# 1_ATMEGA_328P_AU.net
KiCad netlist of a schematic drawn in EAGLE
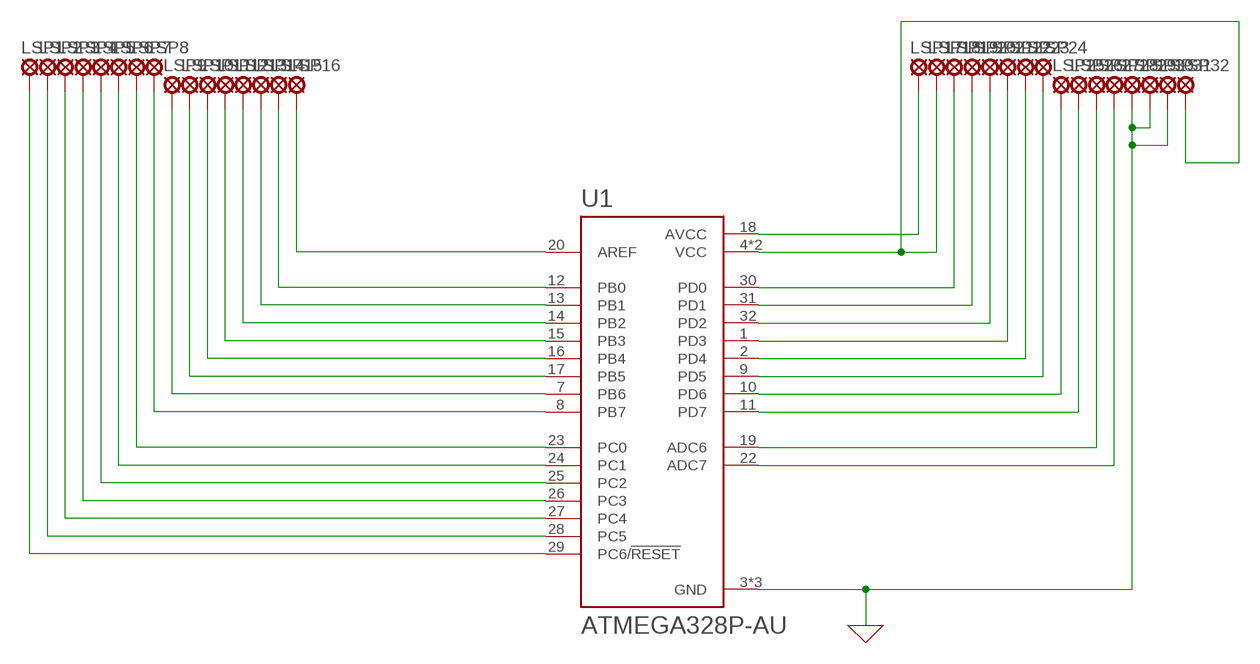
[diagram p0: schematic, sheet 1]

(export (version "E")
  (design (tool "Eeschema 10.0.6"))
  (components
    (comp (ref "LSP1")
      (value "LSP10_CLSP10_C")
      (footprint "eagle-import:LSP10_C")
      (libsource (lib "eagle-import") (part "LSP10_CLSP10_C"))
    )
    (comp (ref "LSP2")
      (value "LSP10_CLSP10_C")
      (footprint "eagle-import:LSP10_C")
      (libsource (lib "eagle-import") (part "LSP10_CLSP10_C"))
    )
    (comp (ref "LSP3")
      (value "LSP10_CLSP10_C")
      (footprint "eagle-import:LSP10_C")
      (libsource (lib "eagle-import") (part "LSP10_CLSP10_C"))
    )
    (comp (ref "LSP4")
      (value "LSP10_CLSP10_C")
      (footprint "eagle-import:LSP10_C")
      (libsource (lib "eagle-import") (part "LSP10_CLSP10_C"))
    )
    (comp (ref "LSP5")
      (value "LSP10_CLSP10_C")
      (footprint "eagle-import:LSP10_C")
      (libsource (lib "eagle-import") (part "LSP10_CLSP10_C"))
    )
    (comp (ref "LSP6")
      (value "LSP10_CLSP10_C")
      (footprint "eagle-import:LSP10_C")
      (libsource (lib "eagle-import") (part "LSP10_CLSP10_C"))
    )
    (comp (ref "LSP7")
      (value "LSP10_CLSP10_C")
      (footprint "eagle-import:LSP10_C")
      (libsource (lib "eagle-import") (part "LSP10_CLSP10_C"))
    )
    (comp (ref "LSP8")
      (value "LSP10_CLSP10_C")
      (footprint "eagle-import:LSP10_C")
      (libsource (lib "eagle-import") (part "LSP10_CLSP10_C"))
    )
    (comp (ref "LSP9")
      (value "LSP10_CLSP10_C")
      (footprint "eagle-import:LSP10_C")
      (libsource (lib "eagle-import") (part "LSP10_CLSP10_C"))
    )
    (comp (ref "LSP10")
      (value "LSP10_CLSP10_C")
      (footprint "eagle-import:LSP10_C")
      (libsource (lib "eagle-import") (part "LSP10_CLSP10_C"))
    )
    (comp (ref "LSP11")
      (value "LSP10_CLSP10_C")
      (footprint "eagle-import:LSP10_C")
      (libsource (lib "eagle-import") (part "LSP10_CLSP10_C"))
    )
    (comp (ref "LSP12")
      (value "LSP10_CLSP10_C")
      (footprint "eagle-import:LSP10_C")
      (libsource (lib "eagle-import") (part "LSP10_CLSP10_C"))
    )
    (comp (ref "LSP13")
      (value "LSP10_CLSP10_C")
      (footprint "eagle-import:LSP10_C")
      (libsource (lib "eagle-import") (part "LSP10_CLSP10_C"))
    )
    (comp (ref "LSP14")
      (value "LSP10_CLSP10_C")
      (footprint "eagle-import:LSP10_C")
      (libsource (lib "eagle-import") (part "LSP10_CLSP10_C"))
    )
    (comp (ref "LSP15")
      (value "LSP10_CLSP10_C")
      (footprint "eagle-import:LSP10_C")
      (libsource (lib "eagle-import") (part "LSP10_CLSP10_C"))
    )
    (comp (ref "LSP16")
      (value "LSP10_CLSP10_C")
      (footprint "eagle-import:LSP10_C")
      (libsource (lib "eagle-import") (part "LSP10_CLSP10_C"))
    )
    (comp (ref "LSP17")
      (value "LSP10_CLSP10_C")
      (footprint "eagle-import:LSP10_C")
      (libsource (lib "eagle-import") (part "LSP10_CLSP10_C"))
    )
    (comp (ref "LSP18")
      (value "LSP10_CLSP10_C")
      (footprint "eagle-import:LSP10_C")
      (libsource (lib "eagle-import") (part "LSP10_CLSP10_C"))
    )
    (comp (ref "LSP19")
      (value "LSP10_CLSP10_C")
      (footprint "eagle-import:LSP10_C")
      (libsource (lib "eagle-import") (part "LSP10_CLSP10_C"))
    )
    (comp (ref "LSP20")
      (value "LSP10_CLSP10_C")
      (footprint "eagle-import:LSP10_C")
      (libsource (lib "eagle-import") (part "LSP10_CLSP10_C"))
    )
    (comp (ref "LSP21")
      (value "LSP10_CLSP10_C")
      (footprint "eagle-import:LSP10_C")
      (libsource (lib "eagle-import") (part "LSP10_CLSP10_C"))
    )
    (comp (ref "LSP22")
      (value "LSP10_CLSP10_C")
      (footprint "eagle-import:LSP10_C")
      (libsource (lib "eagle-import") (part "LSP10_CLSP10_C"))
    )
    (comp (ref "LSP23")
      (value "LSP10_CLSP10_C")
      (footprint "eagle-import:LSP10_C")
      (libsource (lib "eagle-import") (part "LSP10_CLSP10_C"))
    )
    (comp (ref "LSP24")
      (value "LSP10_CLSP10_C")
      (footprint "eagle-import:LSP10_C")
      (libsource (lib "eagle-import") (part "LSP10_CLSP10_C"))
    )
    (comp (ref "LSP25")
      (value "LSP10_CLSP10_C")
      (footprint "eagle-import:LSP10_C")
      (libsource (lib "eagle-import") (part "LSP10_CLSP10_C"))
    )
    (comp (ref "LSP26")
      (value "LSP10_CLSP10_C")
      (footprint "eagle-import:LSP10_C")
      (libsource (lib "eagle-import") (part "LSP10_CLSP10_C"))
    )
    (comp (ref "LSP27")
      (value "LSP10_CLSP10_C")
      (footprint "eagle-import:LSP10_C")
      (libsource (lib "eagle-import") (part "LSP10_CLSP10_C"))
    )
    (comp (ref "LSP28")
      (value "LSP10_CLSP10_C")
      (footprint "eagle-import:LSP10_C")
      (libsource (lib "eagle-import") (part "LSP10_CLSP10_C"))
    )
    (comp (ref "LSP29")
      (value "LSP10_CLSP10_C")
      (footprint "eagle-import:LSP10_C")
      (libsource (lib "eagle-import") (part "LSP10_CLSP10_C"))
    )
    (comp (ref "LSP30")
      (value "LSP10_CLSP10_C")
      (footprint "eagle-import:LSP10_C")
      (libsource (lib "eagle-import") (part "LSP10_CLSP10_C"))
    )
    (comp (ref "LSP31")
      (value "LSP10_CLSP10_C")
      (footprint "eagle-import:LSP10_C")
      (libsource (lib "eagle-import") (part "LSP10_CLSP10_C"))
    )
    (comp (ref "LSP32")
      (value "LSP10_CLSP10_C")
      (footprint "eagle-import:LSP10_C")
      (libsource (lib "eagle-import") (part "LSP10_CLSP10_C"))
    )
    (comp (ref "U1")
      (value "ATMEGA328P-AU")
      (footprint "eagle-import:QFP80P900X900X120-32N")
      (fields (field (name "MF") "Microchip"))
      (libsource (lib "eagle-import") (part "ATMEGA328P-AU"))
    )
  )
  (nets
    (net (code "1") (name "GND") (class "Default")
      (node (ref "LSP29") (pin "P$1") (pinfunction "MP_P$1") (pintype "passive"))
      (node (ref "LSP30") (pin "P$1") (pinfunction "MP_P$1") (pintype "passive"))
      (node (ref "LSP31") (pin "P$1") (pinfunction "MP_P$1") (pintype "passive"))
      (node (ref "U1") (pin "21") (pinfunction "GND_21") (pintype "power_in"))
      (node (ref "U1") (pin "3") (pinfunction "GND_3") (pintype "power_in"))
      (node (ref "U1") (pin "5") (pinfunction "GND_5") (pintype "power_in"))
    )
    (net (code "2") (name "Net-(LSP1-MP)") (class "Default")
      (node (ref "LSP1") (pin "P$1") (pinfunction "MP_P$1") (pintype "passive"))
      (node (ref "U1") (pin "29") (pinfunction "PC6/~{RESET}_29") (pintype "bidirectional"))
    )
    (net (code "3") (name "Net-(LSP2-MP)") (class "Default")
      (node (ref "LSP2") (pin "P$1") (pinfunction "MP_P$1") (pintype "passive"))
      (node (ref "U1") (pin "28") (pinfunction "PC5_28") (pintype "bidirectional"))
    )
    (net (code "4") (name "Net-(LSP3-MP)") (class "Default")
      (node (ref "LSP3") (pin "P$1") (pinfunction "MP_P$1") (pintype "passive"))
      (node (ref "U1") (pin "27") (pinfunction "PC4_27") (pintype "bidirectional"))
    )
    (net (code "5") (name "Net-(LSP4-MP)") (class "Default")
      (node (ref "LSP4") (pin "P$1") (pinfunction "MP_P$1") (pintype "passive"))
      (node (ref "U1") (pin "26") (pinfunction "PC3_26") (pintype "bidirectional"))
    )
    (net (code "6") (name "Net-(LSP5-MP)") (class "Default")
      (node (ref "LSP5") (pin "P$1") (pinfunction "MP_P$1") (pintype "passive"))
      (node (ref "U1") (pin "25") (pinfunction "PC2_25") (pintype "bidirectional"))
    )
    (net (code "7") (name "Net-(LSP6-MP)") (class "Default")
      (node (ref "LSP6") (pin "P$1") (pinfunction "MP_P$1") (pintype "passive"))
      (node (ref "U1") (pin "24") (pinfunction "PC1_24") (pintype "bidirectional"))
    )
    (net (code "8") (name "Net-(LSP7-MP)") (class "Default")
      (node (ref "LSP7") (pin "P$1") (pinfunction "MP_P$1") (pintype "passive"))
      (node (ref "U1") (pin "23") (pinfunction "PC0_23") (pintype "bidirectional"))
    )
    (net (code "9") (name "Net-(LSP8-MP)") (class "Default")
      (node (ref "LSP8") (pin "P$1") (pinfunction "MP_P$1") (pintype "passive"))
      (node (ref "U1") (pin "8") (pinfunction "PB7_8") (pintype "bidirectional"))
    )
    (net (code "10") (name "Net-(LSP9-MP)") (class "Default")
      (node (ref "LSP9") (pin "P$1") (pinfunction "MP_P$1") (pintype "passive"))
      (node (ref "U1") (pin "7") (pinfunction "PB6_7") (pintype "bidirectional"))
    )
    (net (code "11") (name "Net-(LSP10-MP)") (class "Default")
      (node (ref "LSP10") (pin "P$1") (pinfunction "MP_P$1") (pintype "passive"))
      (node (ref "U1") (pin "17") (pinfunction "PB5_17") (pintype "bidirectional"))
    )
    (net (code "12") (name "Net-(LSP11-MP)") (class "Default")
      (node (ref "LSP11") (pin "P$1") (pinfunction "MP_P$1") (pintype "passive"))
      (node (ref "U1") (pin "16") (pinfunction "PB4_16") (pintype "bidirectional"))
    )
    (net (code "13") (name "Net-(LSP12-MP)") (class "Default")
      (node (ref "LSP12") (pin "P$1") (pinfunction "MP_P$1") (pintype "passive"))
      (node (ref "U1") (pin "15") (pinfunction "PB3_15") (pintype "bidirectional"))
    )
    (net (code "14") (name "Net-(LSP13-MP)") (class "Default")
      (node (ref "LSP13") (pin "P$1") (pinfunction "MP_P$1") (pintype "passive"))
      (node (ref "U1") (pin "14") (pinfunction "PB2_14") (pintype "bidirectional"))
    )
    (net (code "15") (name "Net-(LSP14-MP)") (class "Default")
      (node (ref "LSP14") (pin "P$1") (pinfunction "MP_P$1") (pintype "passive"))
      (node (ref "U1") (pin "13") (pinfunction "PB1_13") (pintype "bidirectional"))
    )
    (net (code "16") (name "Net-(LSP15-MP)") (class "Default")
      (node (ref "LSP15") (pin "P$1") (pinfunction "MP_P$1") (pintype "passive"))
      (node (ref "U1") (pin "12") (pinfunction "PB0_12") (pintype "bidirectional"))
    )
    (net (code "17") (name "Net-(LSP16-MP)") (class "Default")
      (node (ref "LSP16") (pin "P$1") (pinfunction "MP_P$1") (pintype "passive"))
      (node (ref "U1") (pin "20") (pinfunction "AREF_20") (pintype "input"))
    )
    (net (code "18") (name "Net-(LSP17-MP)") (class "Default")
      (node (ref "LSP17") (pin "P$1") (pinfunction "MP_P$1") (pintype "passive"))
      (node (ref "U1") (pin "18") (pinfunction "AVCC_18") (pintype "power_in"))
    )
    (net (code "19") (name "Net-(LSP18-MP)") (class "Default")
      (node (ref "LSP18") (pin "P$1") (pinfunction "MP_P$1") (pintype "passive"))
      (node (ref "LSP32") (pin "P$1") (pinfunction "MP_P$1") (pintype "passive"))
      (node (ref "U1") (pin "4") (pinfunction "VCC_4") (pintype "power_in"))
      (node (ref "U1") (pin "6") (pinfunction "VCC_6") (pintype "power_in"))
    )
    (net (code "20") (name "Net-(LSP19-MP)") (class "Default")
      (node (ref "LSP19") (pin "P$1") (pinfunction "MP_P$1") (pintype "passive"))
      (node (ref "U1") (pin "30") (pinfunction "PD0_30") (pintype "bidirectional"))
    )
    (net (code "21") (name "Net-(LSP20-MP)") (class "Default")
      (node (ref "LSP20") (pin "P$1") (pinfunction "MP_P$1") (pintype "passive"))
      (node (ref "U1") (pin "31") (pinfunction "PD1_31") (pintype "bidirectional"))
    )
    (net (code "22") (name "Net-(LSP21-MP)") (class "Default")
      (node (ref "LSP21") (pin "P$1") (pinfunction "MP_P$1") (pintype "passive"))
      (node (ref "U1") (pin "32") (pinfunction "PD2_32") (pintype "bidirectional"))
    )
    (net (code "23") (name "Net-(LSP22-MP)") (class "Default")
      (node (ref "LSP22") (pin "P$1") (pinfunction "MP_P$1") (pintype "passive"))
      (node (ref "U1") (pin "1") (pinfunction "PD3_1") (pintype "bidirectional"))
    )
    (net (code "24") (name "Net-(LSP23-MP)") (class "Default")
      (node (ref "LSP23") (pin "P$1") (pinfunction "MP_P$1") (pintype "passive"))
      (node (ref "U1") (pin "2") (pinfunction "PD4_2") (pintype "bidirectional"))
    )
    (net (code "25") (name "Net-(LSP24-MP)") (class "Default")
      (node (ref "LSP24") (pin "P$1") (pinfunction "MP_P$1") (pintype "passive"))
      (node (ref "U1") (pin "9") (pinfunction "PD5_9") (pintype "bidirectional"))
    )
    (net (code "26") (name "Net-(LSP25-MP)") (class "Default")
      (node (ref "LSP25") (pin "P$1") (pinfunction "MP_P$1") (pintype "passive"))
      (node (ref "U1") (pin "10") (pinfunction "PD6_10") (pintype "bidirectional"))
    )
    (net (code "27") (name "Net-(LSP26-MP)") (class "Default")
      (node (ref "LSP26") (pin "P$1") (pinfunction "MP_P$1") (pintype "passive"))
      (node (ref "U1") (pin "11") (pinfunction "PD7_11") (pintype "bidirectional"))
    )
    (net (code "28") (name "Net-(LSP27-MP)") (class "Default")
      (node (ref "LSP27") (pin "P$1") (pinfunction "MP_P$1") (pintype "passive"))
      (node (ref "U1") (pin "19") (pinfunction "ADC6_19") (pintype "bidirectional"))
    )
    (net (code "29") (name "Net-(LSP28-MP)") (class "Default")
      (node (ref "LSP28") (pin "P$1") (pinfunction "MP_P$1") (pintype "passive"))
      (node (ref "U1") (pin "22") (pinfunction "ADC7_22") (pintype "bidirectional"))
    )
  )
)
